# Switchcontroller.net
KiCad netlist of a schematic drawn in EAGLE
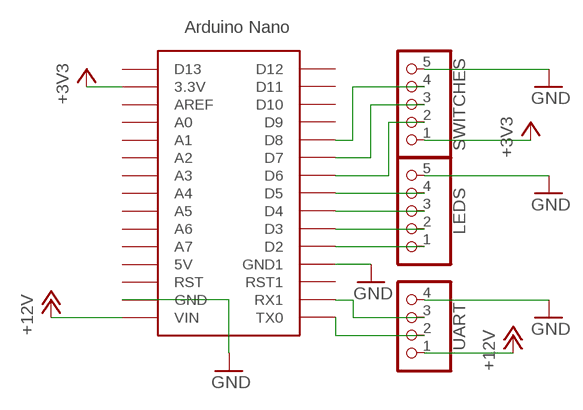
[diagram p0: schematic, sheet 1]

(export (version "E")
  (design (tool "Eeschema 10.0.6"))
  (components
    (comp (ref "LEDS")
      (value "PINHD-1X5")
      (footprint "eagle-import:1X05")
      (libsource (lib "eagle-import") (part "PINHD-1X5"))
    )
    (comp (ref "SWITCHES")
      (value "PINHD-1X5")
      (footprint "eagle-import:1X05")
      (libsource (lib "eagle-import") (part "PINHD-1X5"))
    )
    (comp (ref "U$1")
      (value "NANO_DIL_RECEPTORPIN-M1")
      (footprint "eagle-import:NANO_DIL_M1")
      (libsource (lib "eagle-import") (part "NANO_DIL_RECEPTORPIN-M1"))
    )
    (comp (ref "UART")
      (value "PINHD-1X4")
      (footprint "eagle-import:1X04")
      (libsource (lib "eagle-import") (part "PINHD-1X4"))
    )
  )
  (nets
    (net (code "1") (name "+3V3") (class "Default")
      (node (ref "SWITCHES") (pin "1") (pinfunction "1_1") (pintype "passive"))
      (node (ref "U$1") (pin "3.3V") (pinfunction "3.3V_3.3V") (pintype "bidirectional"))
    )
    (net (code "2") (name "+12V") (class "Default")
      (node (ref "U$1") (pin "VIN") (pinfunction "VIN_VIN") (pintype "bidirectional"))
      (node (ref "UART") (pin "1") (pinfunction "1_1") (pintype "passive"))
    )
    (net (code "3") (name "GND") (class "Default")
      (node (ref "LEDS") (pin "5") (pinfunction "5_5") (pintype "passive"))
      (node (ref "SWITCHES") (pin "5") (pinfunction "5_5") (pintype "passive"))
      (node (ref "U$1") (pin "GND") (pinfunction "GND_GND") (pintype "bidirectional"))
      (node (ref "U$1") (pin "GND1") (pinfunction "GND1_GND1") (pintype "bidirectional"))
      (node (ref "UART") (pin "4") (pinfunction "4_4") (pintype "passive"))
    )
    (net (code "4") (name "Net-(LEDS-Pad1)") (class "Default")
      (node (ref "LEDS") (pin "1") (pinfunction "1_1") (pintype "passive"))
      (node (ref "U$1") (pin "D2") (pinfunction "D2_D2") (pintype "bidirectional"))
    )
    (net (code "5") (name "Net-(LEDS-Pad2)") (class "Default")
      (node (ref "LEDS") (pin "2") (pinfunction "2_2") (pintype "passive"))
      (node (ref "U$1") (pin "D3") (pinfunction "D3_D3") (pintype "bidirectional"))
    )
    (net (code "6") (name "Net-(LEDS-Pad3)") (class "Default")
      (node (ref "LEDS") (pin "3") (pinfunction "3_3") (pintype "passive"))
      (node (ref "U$1") (pin "D4") (pinfunction "D4_D4") (pintype "bidirectional"))
    )
    (net (code "7") (name "Net-(LEDS-Pad4)") (class "Default")
      (node (ref "LEDS") (pin "4") (pinfunction "4_4") (pintype "passive"))
      (node (ref "U$1") (pin "D5") (pinfunction "D5_D5") (pintype "bidirectional"))
    )
    (net (code "8") (name "Net-(SWITCHES-Pad2)") (class "Default")
      (node (ref "SWITCHES") (pin "2") (pinfunction "2_2") (pintype "passive"))
      (node (ref "U$1") (pin "D6") (pinfunction "D6_D6") (pintype "bidirectional"))
    )
    (net (code "9") (name "Net-(SWITCHES-Pad3)") (class "Default")
      (node (ref "SWITCHES") (pin "3") (pinfunction "3_3") (pintype "passive"))
      (node (ref "U$1") (pin "D7") (pinfunction "D7_D7") (pintype "bidirectional"))
    )
    (net (code "10") (name "Net-(SWITCHES-Pad4)") (class "Default")
      (node (ref "SWITCHES") (pin "4") (pinfunction "4_4") (pintype "passive"))
      (node (ref "U$1") (pin "D8") (pinfunction "D8_D8") (pintype "bidirectional"))
    )
    (net (code "11") (name "Net-(U$1-PadRX1)") (class "Default")
      (node (ref "U$1") (pin "RX1") (pinfunction "RX1_RX1") (pintype "bidirectional"))
      (node (ref "UART") (pin "3") (pinfunction "3_3") (pintype "passive"))
    )
    (net (code "12") (name "Net-(U$1-PadTX0)") (class "Default")
      (node (ref "U$1") (pin "TX0") (pinfunction "TX0_TX0") (pintype "bidirectional"))
      (node (ref "UART") (pin "2") (pinfunction "2_2") (pintype "passive"))
    )
    (net (code "13") (name "unconnected-(U$1-Pad5V)") (class "Default")
      (node (ref "U$1") (pin "5V") (pinfunction "5V_5V") (pintype "bidirectional"))
    )
    (net (code "14") (name "unconnected-(U$1-PadA0)") (class "Default")
      (node (ref "U$1") (pin "A0") (pinfunction "A0_A0") (pintype "bidirectional"))
    )
    (net (code "15") (name "unconnected-(U$1-PadA1)") (class "Default")
      (node (ref "U$1") (pin "A1") (pinfunction "A1_A1") (pintype "bidirectional"))
    )
    (net (code "16") (name "unconnected-(U$1-PadA2)") (class "Default")
      (node (ref "U$1") (pin "A2") (pinfunction "A2_A2") (pintype "bidirectional"))
    )
    (net (code "17") (name "unconnected-(U$1-PadA3)") (class "Default")
      (node (ref "U$1") (pin "A3") (pinfunction "A3_A3") (pintype "bidirectional"))
    )
    (net (code "18") (name "unconnected-(U$1-PadA4)") (class "Default")
      (node (ref "U$1") (pin "A4") (pinfunction "A4_A4") (pintype "bidirectional"))
    )
    (net (code "19") (name "unconnected-(U$1-PadA5)") (class "Default")
      (node (ref "U$1") (pin "A5") (pinfunction "A5_A5") (pintype "bidirectional"))
    )
    (net (code "20") (name "unconnected-(U$1-PadA6)") (class "Default")
      (node (ref "U$1") (pin "A6") (pinfunction "A6_A6") (pintype "bidirectional"))
    )
    (net (code "21") (name "unconnected-(U$1-PadA7)") (class "Default")
      (node (ref "U$1") (pin "A7") (pinfunction "A7_A7") (pintype "bidirectional"))
    )
    (net (code "22") (name "unconnected-(U$1-PadAREF)") (class "Default")
      (node (ref "U$1") (pin "AREF") (pinfunction "AREF_AREF") (pintype "bidirectional"))
    )
    (net (code "23") (name "unconnected-(U$1-PadD9)") (class "Default")
      (node (ref "U$1") (pin "D9") (pinfunction "D9_D9") (pintype "bidirectional"))
    )
    (net (code "24") (name "unconnected-(U$1-PadD10)") (class "Default")
      (node (ref "U$1") (pin "D10") (pinfunction "D10_D10") (pintype "bidirectional"))
    )
    (net (code "25") (name "unconnected-(U$1-PadD11)") (class "Default")
      (node (ref "U$1") (pin "D11") (pinfunction "D11_D11") (pintype "bidirectional"))
    )
    (net (code "26") (name "unconnected-(U$1-PadD12)") (class "Default")
      (node (ref "U$1") (pin "D12") (pinfunction "D12_D12") (pintype "bidirectional"))
    )
    (net (code "27") (name "unconnected-(U$1-PadD13)") (class "Default")
      (node (ref "U$1") (pin "D13") (pinfunction "D13_D13") (pintype "bidirectional"))
    )
    (net (code "28") (name "unconnected-(U$1-PadRST)") (class "Default")
      (node (ref "U$1") (pin "RST") (pinfunction "RST_RST") (pintype "bidirectional"))
    )
    (net (code "29") (name "unconnected-(U$1-PadRST1)") (class "Default")
      (node (ref "U$1") (pin "RST1") (pinfunction "RST1_RST1") (pintype "bidirectional"))
    )
  )
)
